# wind_speed.net
KiCad netlist of a schematic drawn in EAGLE
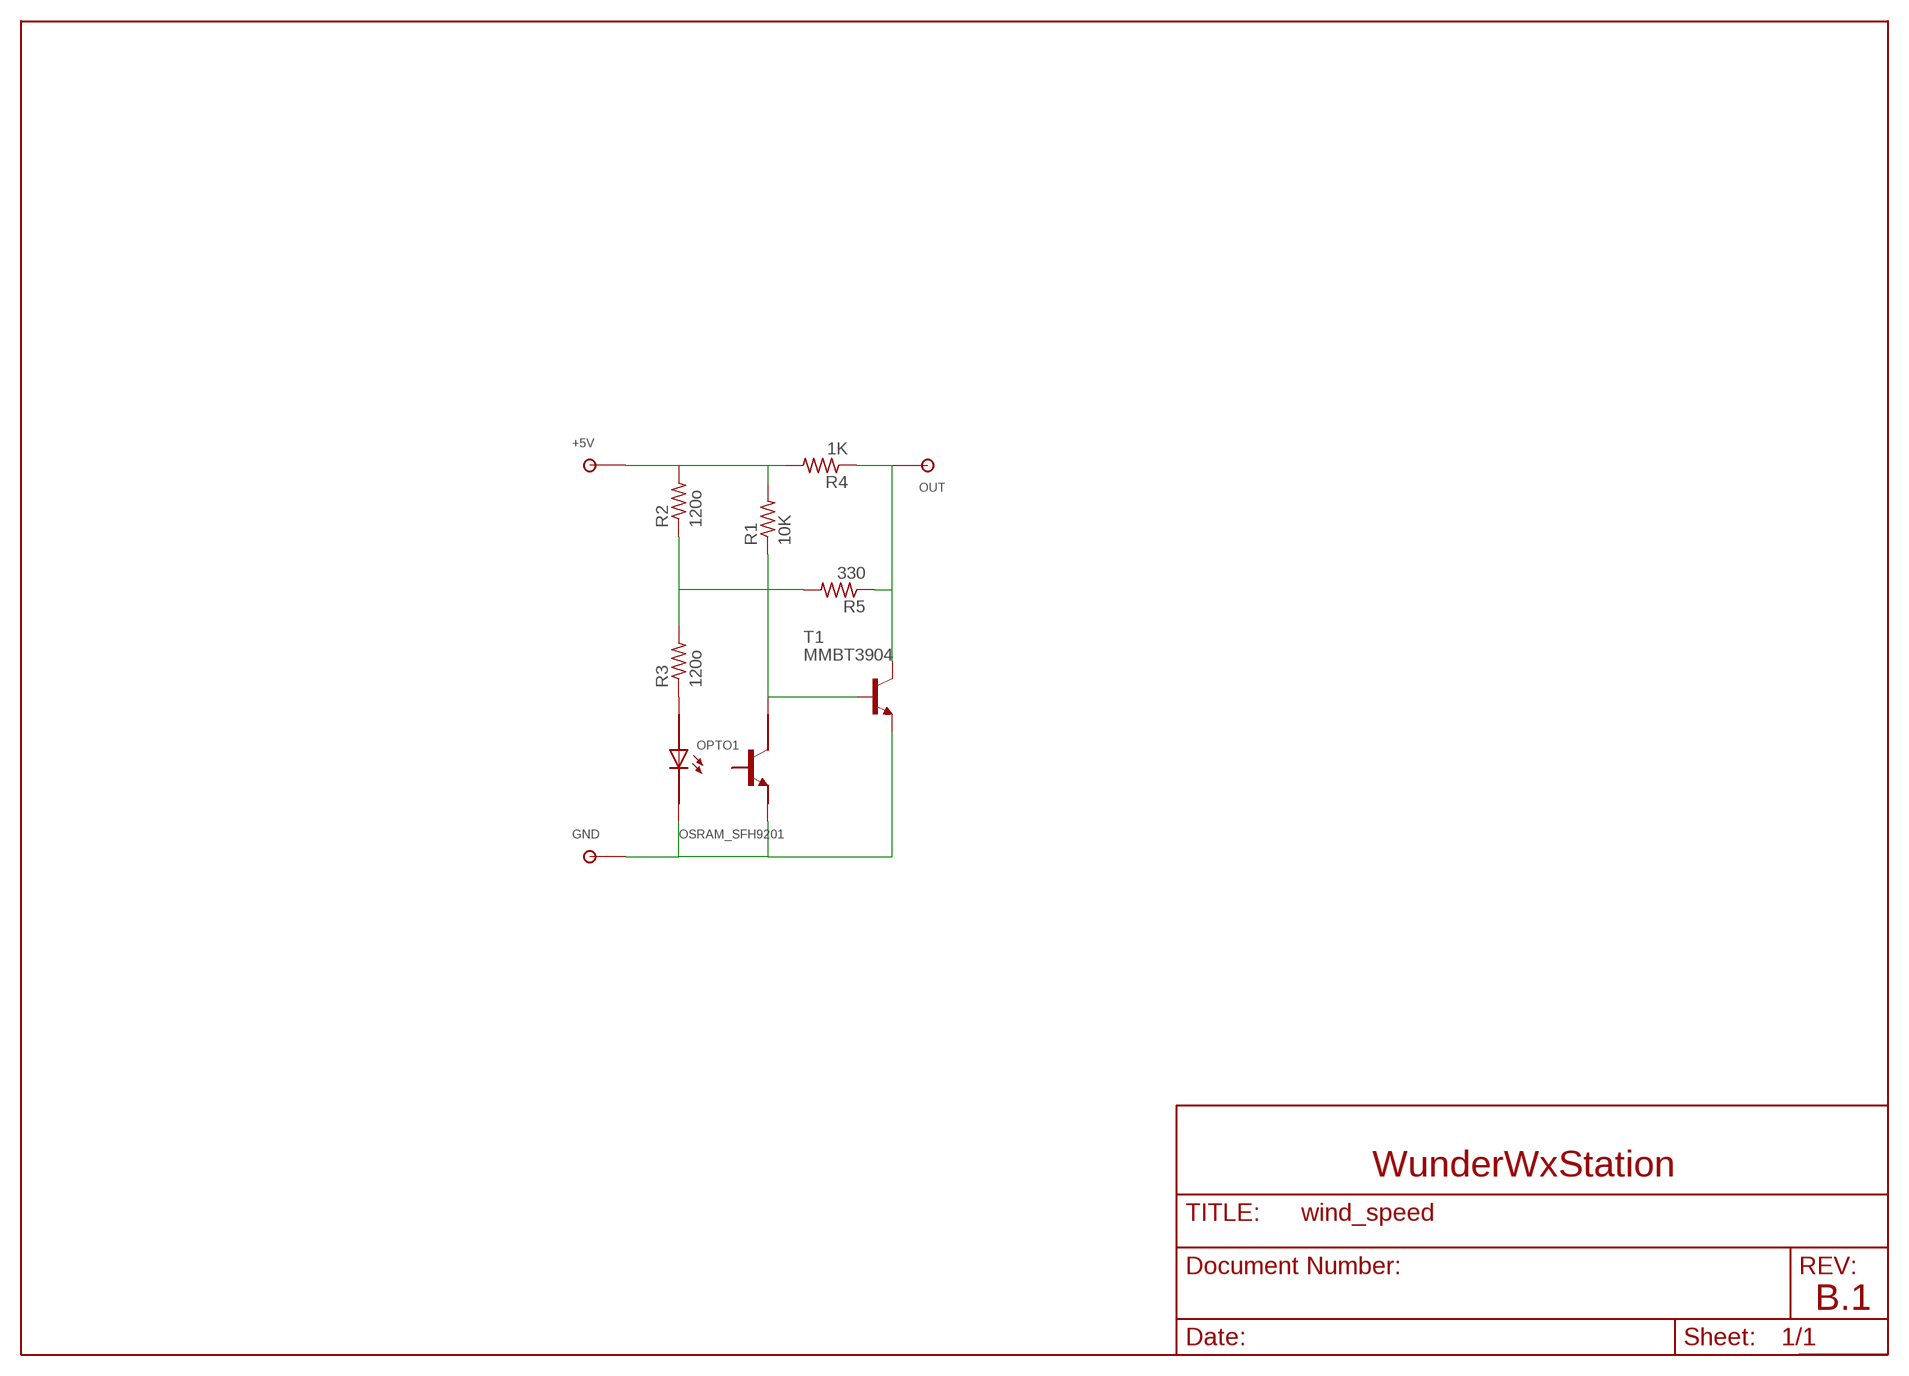
[diagram p0: schematic, sheet 1]

(export (version "E")
  (design (tool "Eeschema 10.0.6"))
  (components
    (comp (ref "+5V")
      (value "TPSOL")
      (footprint "eagle-import:TP_SOL")
      (libsource (lib "eagle-import") (part "TPSOL"))
    )
    (comp (ref "GND")
      (value "TPSOL")
      (footprint "eagle-import:TP_SOL")
      (libsource (lib "eagle-import") (part "TPSOL"))
    )
    (comp (ref "OPTO1")
      (value "OSRAM_SFH9201")
      (footprint "eagle-import:OSRAM-6")
      (libsource (lib "eagle-import") (part "OSRAM_SHF9201"))
    )
    (comp (ref "OUT")
      (value "TPSOL")
      (footprint "eagle-import:TP_SOL")
      (libsource (lib "eagle-import") (part "TPSOL"))
    )
    (comp (ref "R1")
      (value "10K")
      (footprint "eagle-import:R0603")
      (libsource (lib "eagle-import") (part "R-US_R0603"))
    )
    (comp (ref "R2")
      (value "120o")
      (footprint "eagle-import:R0603")
      (libsource (lib "eagle-import") (part "R-US_R0603"))
    )
    (comp (ref "R3")
      (value "120o")
      (footprint "eagle-import:R0603")
      (libsource (lib "eagle-import") (part "R-US_R0603"))
    )
    (comp (ref "R4")
      (value "1K")
      (footprint "eagle-import:R0603")
      (libsource (lib "eagle-import") (part "R-US_R0603"))
    )
    (comp (ref "R5")
      (value "330")
      (footprint "eagle-import:R0603")
      (libsource (lib "eagle-import") (part "R-US_R0603"))
    )
    (comp (ref "T1")
      (value "MMBT3904")
      (footprint "eagle-import:SOT23")
      (libsource (lib "eagle-import") (part "BC846"))
    )
  )
  (nets
    (net (code "1") (name "Net-(+5V-PadP$1)") (class "Default")
      (node (ref "+5V") (pin "P$1") (pinfunction "P$1_P$1") (pintype "bidirectional"))
      (node (ref "R1") (pin "2") (pinfunction "2_2") (pintype "passive"))
      (node (ref "R2") (pin "2") (pinfunction "2_2") (pintype "passive"))
      (node (ref "R4") (pin "2") (pinfunction "2_2") (pintype "passive"))
    )
    (net (code "2") (name "Net-(OPTO1-AN)") (class "Default")
      (node (ref "OPTO1") (pin "P$1") (pinfunction "AN_P$1") (pintype "passive"))
      (node (ref "R3") (pin "1") (pinfunction "1_1") (pintype "passive"))
    )
    (net (code "3") (name "Net-(OPTO1-C)") (class "Default")
      (node (ref "OPTO1") (pin "P$4") (pinfunction "C_P$4") (pintype "passive"))
      (node (ref "R1") (pin "1") (pinfunction "1_1") (pintype "passive"))
      (node (ref "T1") (pin "1") (pinfunction "B_1") (pintype "passive"))
    )
    (net (code "4") (name "Net-(OPTO1-CATH)") (class "Default")
      (node (ref "GND") (pin "P$1") (pinfunction "P$1_P$1") (pintype "bidirectional"))
      (node (ref "OPTO1") (pin "P$3") (pinfunction "E_P$3") (pintype "passive"))
      (node (ref "OPTO1") (pin "P$6") (pinfunction "CATH_P$6") (pintype "passive"))
      (node (ref "T1") (pin "2") (pinfunction "E_2") (pintype "passive"))
    )
    (net (code "5") (name "Net-(R2-Pad1)") (class "Default")
      (node (ref "R2") (pin "1") (pinfunction "1_1") (pintype "passive"))
      (node (ref "R3") (pin "2") (pinfunction "2_2") (pintype "passive"))
      (node (ref "R5") (pin "2") (pinfunction "2_2") (pintype "passive"))
    )
    (net (code "6") (name "Net-(T1-C)") (class "Default")
      (node (ref "OUT") (pin "P$1") (pinfunction "P$1_P$1") (pintype "bidirectional"))
      (node (ref "R4") (pin "1") (pinfunction "1_1") (pintype "passive"))
      (node (ref "R5") (pin "1") (pinfunction "1_1") (pintype "passive"))
      (node (ref "T1") (pin "3") (pinfunction "C_3") (pintype "passive"))
    )
    (net (code "7") (name "unconnected-(OPTO1-P$2-PadP$5)") (class "Default")
      (node (ref "OPTO1") (pin "P$5") (pinfunction "P$2_P$5") (pintype "no_connect"))
    )
    (net (code "8") (name "unconnected-(OPTO1-P$5-PadP$2)") (class "Default")
      (node (ref "OPTO1") (pin "P$2") (pinfunction "P$5_P$2") (pintype "no_connect"))
    )
  )
)
